# STM32_Minimum_System.net
KiCad netlist of a schematic drawn in EasyEDA Pro
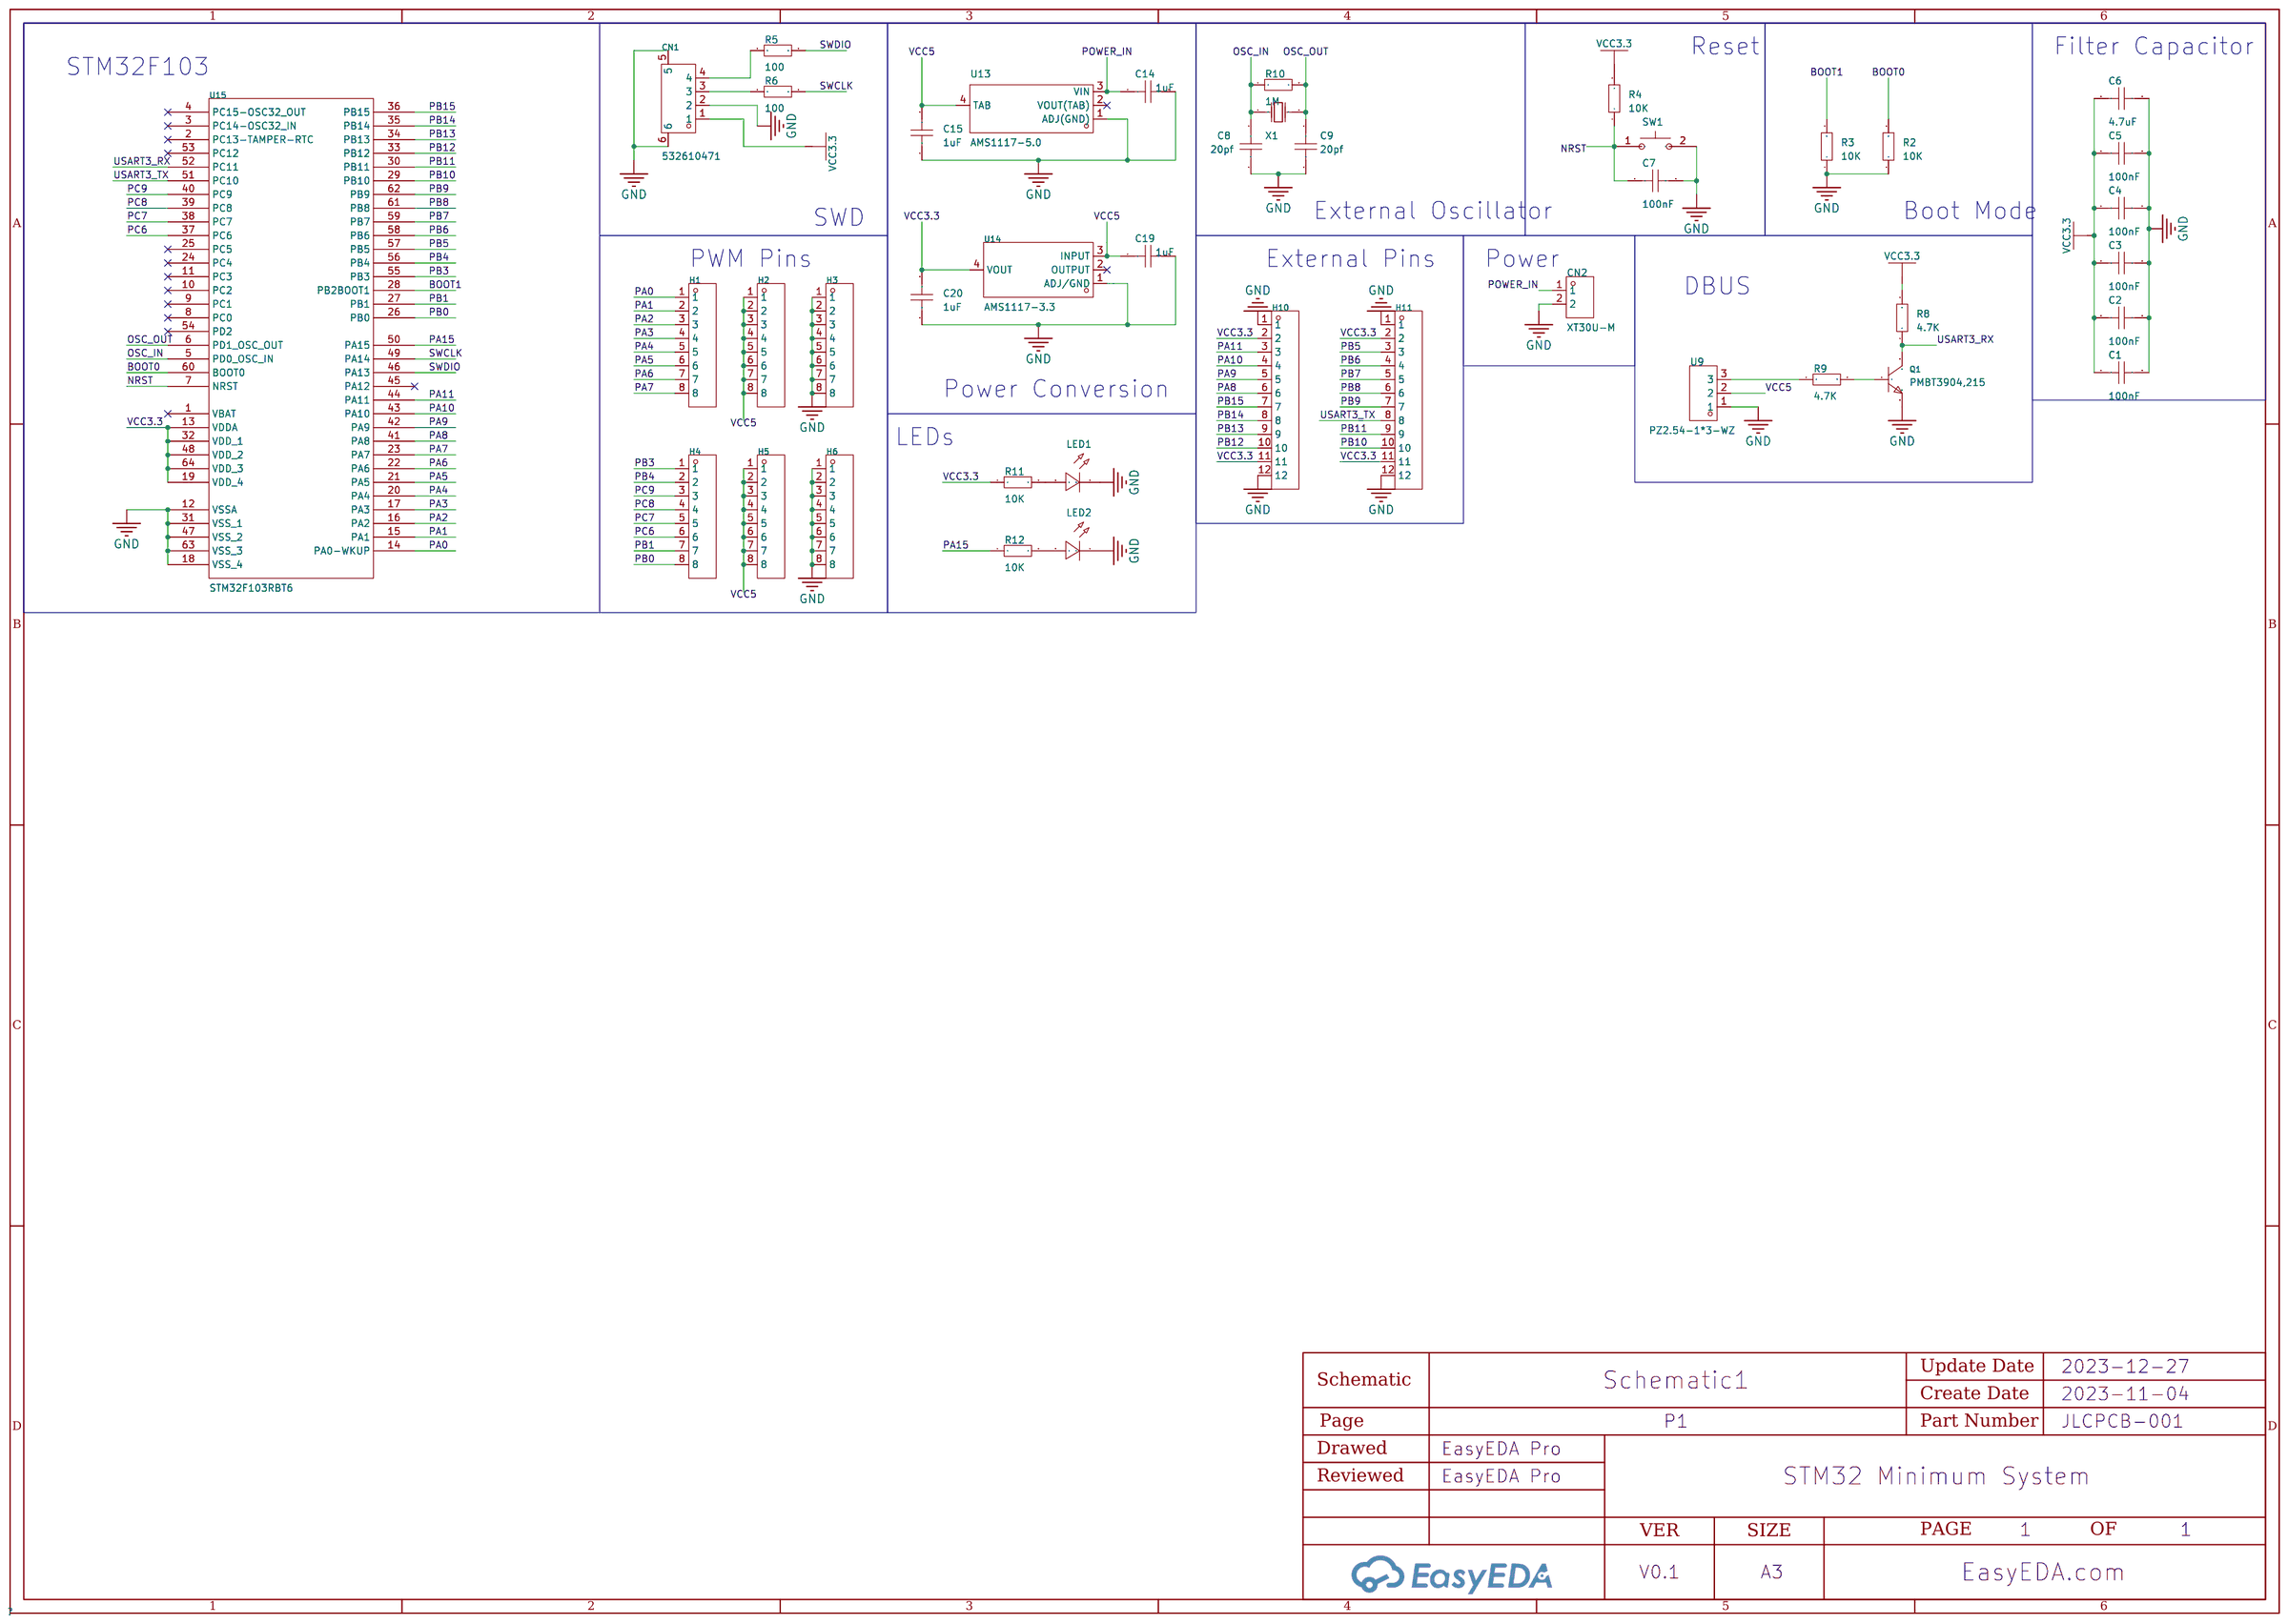
[diagram p0: schematic sheet]

(export (version "E")
  (design (tool "Eeschema 10.0.6"))
  (components
    (comp (ref "C1")
      (value "100nF")
      (footprint "easyedapro:C0603")
      (libsource (lib "easyedapro") (part "CAP"))
    )
    (comp (ref "C2")
      (value "100nF")
      (footprint "easyedapro:C0603")
      (libsource (lib "easyedapro") (part "CAP"))
    )
    (comp (ref "C3")
      (value "100nF")
      (footprint "easyedapro:C0603")
      (libsource (lib "easyedapro") (part "CAP"))
    )
    (comp (ref "C4")
      (value "100nF")
      (footprint "easyedapro:C0603")
      (libsource (lib "easyedapro") (part "CAP"))
    )
    (comp (ref "C5")
      (value "100nF")
      (footprint "easyedapro:C0603")
      (libsource (lib "easyedapro") (part "CAP"))
    )
    (comp (ref "C6")
      (value "4.7uF")
      (footprint "easyedapro:C0603")
      (libsource (lib "easyedapro") (part "CAP"))
    )
    (comp (ref "C7")
      (value "100nF")
      (footprint "easyedapro:C0603")
      (libsource (lib "easyedapro") (part "CAP"))
    )
    (comp (ref "C8")
      (value "20pf")
      (footprint "easyedapro:C0603")
      (libsource (lib "easyedapro") (part "CAP"))
    )
    (comp (ref "C9")
      (value "20pf")
      (footprint "easyedapro:C0603")
      (libsource (lib "easyedapro") (part "CAP"))
    )
    (comp (ref "C14")
      (value "1uF")
      (footprint "easyedapro:C0603")
      (libsource (lib "easyedapro") (part "CAP"))
    )
    (comp (ref "C15")
      (value "1uF")
      (footprint "easyedapro:C0603")
      (libsource (lib "easyedapro") (part "CAP"))
    )
    (comp (ref "C19")
      (value "1uF")
      (footprint "easyedapro:C0603")
      (libsource (lib "easyedapro") (part "CAP"))
    )
    (comp (ref "C20")
      (value "1uF")
      (footprint "easyedapro:C0603")
      (libsource (lib "easyedapro") (part "CAP"))
    )
    (comp (ref "CN1")
      (value "532610471")
      (footprint "easyedapro:CONN-SMD_4P-P1.25_53261-0471")
      (fields (field (name "Manufacturer") "MOLEX"))
      (libsource (lib "easyedapro") (part "53261-0471"))
    )
    (comp (ref "CN2")
      (value "XT30U-M")
      (footprint "easyedapro:CONN-TH_XT30U-M")
      (fields (field (name "Manufacturer") "AMASS(艾迈斯)"))
      (libsource (lib "easyedapro") (part "XT30U-M"))
    )
    (comp (ref "H1")
      (value "KH-2.54PH180-1X8P-L11.5")
      (footprint "easyedapro:HDR-TH_8P-P2.54-V-M")
      (fields (field (name "Manufacturer") "kinghelm(金航标)"))
      (libsource (lib "easyedapro") (part "KH-2.54PH180-1X8P-L11.5"))
    )
    (comp (ref "H2")
      (value "KH-2.54PH180-1X8P-L11.5")
      (footprint "easyedapro:HDR-TH_8P-P2.54-V-M")
      (fields (field (name "Manufacturer") "kinghelm(金航标)"))
      (libsource (lib "easyedapro") (part "KH-2.54PH180-1X8P-L11.5"))
    )
    (comp (ref "H3")
      (value "KH-2.54PH180-1X8P-L11.5")
      (footprint "easyedapro:HDR-TH_8P-P2.54-V-M")
      (fields (field (name "Manufacturer") "kinghelm(金航标)"))
      (libsource (lib "easyedapro") (part "KH-2.54PH180-1X8P-L11.5"))
    )
    (comp (ref "H4")
      (value "KH-2.54PH180-1X8P-L11.5")
      (footprint "easyedapro:HDR-TH_8P-P2.54-V-M")
      (fields (field (name "Manufacturer") "kinghelm(金航标)"))
      (libsource (lib "easyedapro") (part "KH-2.54PH180-1X8P-L11.5"))
    )
    (comp (ref "H5")
      (value "KH-2.54PH180-1X8P-L11.5")
      (footprint "easyedapro:HDR-TH_8P-P2.54-V-M")
      (fields (field (name "Manufacturer") "kinghelm(金航标)"))
      (libsource (lib "easyedapro") (part "KH-2.54PH180-1X8P-L11.5"))
    )
    (comp (ref "H6")
      (value "KH-2.54PH180-1X8P-L11.5")
      (footprint "easyedapro:HDR-TH_8P-P2.54-V-M")
      (fields (field (name "Manufacturer") "kinghelm(金航标)"))
      (libsource (lib "easyedapro") (part "KH-2.54PH180-1X8P-L11.5"))
    )
    (comp (ref "H10")
      (value "KH-2.54PH180-1X12P-L11.5")
      (footprint "easyedapro:HDR-TH_12P-P2.54-V-M")
      (fields (field (name "Manufacturer") "kinghelm(金航标)"))
      (libsource (lib "easyedapro") (part "KH-2.54PH180-1X12P-L11.5"))
    )
    (comp (ref "H11")
      (value "KH-2.54PH180-1X12P-L11.5")
      (footprint "easyedapro:HDR-TH_12P-P2.54-V-M")
      (fields (field (name "Manufacturer") "kinghelm(金航标)"))
      (libsource (lib "easyedapro") (part "KH-2.54PH180-1X12P-L11.5"))
    )
    (comp (ref "LED1")
      (value "~")
      (footprint "easyedapro:LED0603-RD_GREEN")
      (libsource (lib "easyedapro") (part "LED_G"))
    )
    (comp (ref "LED2")
      (value "~")
      (footprint "easyedapro:LED0603-R-RD")
      (libsource (lib "easyedapro") (part "LED_B"))
    )
    (comp (ref "Q1")
      (value "PMBT3904,215")
      (footprint "easyedapro:SOT-23_L2.9-W1.3-P1.90-LS2.4-BR")
      (fields (field (name "Manufacturer") "Nexperia(安世)"))
      (libsource (lib "easyedapro") (part "PMBT3904,215"))
    )
    (comp (ref "R2") (value "10K") (footprint "easyedapro:R0603") (libsource (lib "easyedapro") (part "Res")))
    (comp (ref "R3") (value "10K") (footprint "easyedapro:R0603") (libsource (lib "easyedapro") (part "Res")))
    (comp (ref "R4") (value "10K") (footprint "easyedapro:R0603") (libsource (lib "easyedapro") (part "Res")))
    (comp (ref "R5") (value "100") (footprint "easyedapro:R0603") (libsource (lib "easyedapro") (part "Res")))
    (comp (ref "R6") (value "100") (footprint "easyedapro:R0603") (libsource (lib "easyedapro") (part "Res")))
    (comp (ref "R8")
      (value "4.7K")
      (footprint "easyedapro:R0603")
      (libsource (lib "easyedapro") (part "Res"))
    )
    (comp (ref "R9")
      (value "4.7K")
      (footprint "easyedapro:R0603")
      (libsource (lib "easyedapro") (part "Res"))
    )
    (comp (ref "R10") (value "1M") (footprint "easyedapro:R0603") (libsource (lib "easyedapro") (part "Res")))
    (comp (ref "R11")
      (value "10K")
      (footprint "easyedapro:R0603")
      (libsource (lib "easyedapro") (part "Res"))
    )
    (comp (ref "R12")
      (value "10K")
      (footprint "easyedapro:R0603")
      (libsource (lib "easyedapro") (part "Res"))
    )
    (comp (ref "SW1")
      (value "1TS002C-2300-4300-CT")
      (footprint "easyedapro:SW-SMD_L6.0-W3.5-LS8.0-EH")
      (fields (field (name "Manufacturer") "HYP(鸿源精密)"))
      (libsource (lib "easyedapro") (part "1TS002C-2300-4300"))
    )
    (comp (ref "U9")
      (value "PZ2.54-1*3-WZ")
      (footprint "easyedapro:HDR-TH_3P-P2.54-H-M-W7.7-P")
      (fields (field (name "Manufacturer") "ZHOURI(洲日)"))
      (libsource (lib "easyedapro") (part "PZ2.54-1*3-WZ"))
    )
    (comp (ref "U13")
      (value "AMS1117-5.0")
      (footprint "easyedapro:SOT-223_L6.7-W3.5-P2.30-BR")
      (fields (field (name "Manufacturer") "UMW(广东友台半导体)"))
      (libsource (lib "easyedapro") (part "AMS1117-5.0_C347223"))
    )
    (comp (ref "U14")
      (value "AMS1117-3.3")
      (footprint "easyedapro:SOT-223-3_L6.5-W3.4-P2.30-LS7.0-BR")
      (fields (field (name "Manufacturer") "TECH PUBLIC(台舟)"))
      (libsource (lib "easyedapro") (part "AMS1117-3.3_C18212698"))
    )
    (comp (ref "U15")
      (value "STM32F103RBT6")
      (footprint "easyedapro:LQFP-64_L10.0-W10.0-P0.50-LS12.0-BL")
      (fields (field (name "Manufacturer") "ST(意法半导体)"))
      (libsource (lib "easyedapro") (part "STM32F103RBT6"))
    )
    (comp (ref "X1")
      (value "8MHz")
      (footprint "easyedapro:HC-49US_L11.5-W4.5-P4.88")
      (fields (field (name "Manufacturer Part") "X49SM8MSD2SC") (field (name "Manufacturer") "YXC(扬兴晶振)"))
      (libsource (lib "easyedapro") (part "9B0808LCSC-AAK2S"))
    )
  )
  (nets
    (net (code "1") (name "/BOOT0") (class "Default")
      (node (ref "R2") (pin "2") (pinfunction "2_2") (pintype "input"))
      (node (ref "U15") (pin "60") (pinfunction "BOOT0_60") (pintype "input"))
    )
    (net (code "2") (name "/BOOT1") (class "Default")
      (node (ref "R3") (pin "2") (pinfunction "2_2") (pintype "input"))
      (node (ref "U15") (pin "28") (pinfunction "PB2BOOT1_28") (pintype "input"))
    )
    (net (code "3") (name "/NRST") (class "Default")
      (node (ref "C7") (pin "2") (pinfunction "2_2") (pintype "input"))
      (node (ref "R4") (pin "1") (pinfunction "1_1") (pintype "input"))
      (node (ref "SW1") (pin "1") (pinfunction "A_1") (pintype "input"))
      (node (ref "U15") (pin "7") (pinfunction "NRST_7") (pintype "input"))
    )
    (net (code "4") (name "/OSC_IN") (class "Default")
      (node (ref "C8") (pin "1") (pinfunction "1_1") (pintype "input"))
      (node (ref "R10") (pin "1") (pinfunction "1_1") (pintype "input"))
      (node (ref "U15") (pin "5") (pinfunction "PD0_OSC_IN_5") (pintype "input"))
      (node (ref "X1") (pin "1") (pinfunction "OSC1_1") (pintype "input"))
    )
    (net (code "5") (name "/OSC_OUT") (class "Default")
      (node (ref "C9") (pin "1") (pinfunction "1_1") (pintype "input"))
      (node (ref "R10") (pin "2") (pinfunction "2_2") (pintype "input"))
      (node (ref "U15") (pin "6") (pinfunction "PD1_OSC_OUT_6") (pintype "input"))
      (node (ref "X1") (pin "2") (pinfunction "OSC2_2") (pintype "input"))
    )
    (net (code "6") (name "/PA0") (class "Default")
      (node (ref "H1") (pin "1") (pinfunction "1_1") (pintype "input"))
      (node (ref "U15") (pin "14") (pinfunction "PA0-WKUP_14") (pintype "input"))
    )
    (net (code "7") (name "/PA1") (class "Default")
      (node (ref "H1") (pin "2") (pinfunction "2_2") (pintype "input"))
      (node (ref "U15") (pin "15") (pinfunction "PA1_15") (pintype "input"))
    )
    (net (code "8") (name "/PA2") (class "Default")
      (node (ref "H1") (pin "3") (pinfunction "3_3") (pintype "input"))
      (node (ref "U15") (pin "16") (pinfunction "PA2_16") (pintype "input"))
    )
    (net (code "9") (name "/PA3") (class "Default")
      (node (ref "H1") (pin "4") (pinfunction "4_4") (pintype "input"))
      (node (ref "U15") (pin "17") (pinfunction "PA3_17") (pintype "input"))
    )
    (net (code "10") (name "/PA4") (class "Default")
      (node (ref "H1") (pin "5") (pinfunction "5_5") (pintype "input"))
      (node (ref "U15") (pin "20") (pinfunction "PA4_20") (pintype "input"))
    )
    (net (code "11") (name "/PA5") (class "Default")
      (node (ref "H1") (pin "6") (pinfunction "6_6") (pintype "input"))
      (node (ref "U15") (pin "21") (pinfunction "PA5_21") (pintype "input"))
    )
    (net (code "12") (name "/PA6") (class "Default")
      (node (ref "H1") (pin "7") (pinfunction "7_7") (pintype "input"))
      (node (ref "U15") (pin "22") (pinfunction "PA6_22") (pintype "input"))
    )
    (net (code "13") (name "/PA7") (class "Default")
      (node (ref "H1") (pin "8") (pinfunction "8_8") (pintype "input"))
      (node (ref "U15") (pin "23") (pinfunction "PA7_23") (pintype "input"))
    )
    (net (code "14") (name "/PA8") (class "Default")
      (node (ref "H10") (pin "6") (pinfunction "6_6") (pintype "input"))
      (node (ref "U15") (pin "41") (pinfunction "PA8_41") (pintype "input"))
    )
    (net (code "15") (name "/PA9") (class "Default")
      (node (ref "H10") (pin "5") (pinfunction "5_5") (pintype "input"))
      (node (ref "U15") (pin "42") (pinfunction "PA9_42") (pintype "input"))
    )
    (net (code "16") (name "/PA10") (class "Default")
      (node (ref "H10") (pin "4") (pinfunction "4_4") (pintype "input"))
      (node (ref "U15") (pin "43") (pinfunction "PA10_43") (pintype "input"))
    )
    (net (code "17") (name "/PA11") (class "Default")
      (node (ref "H10") (pin "3") (pinfunction "3_3") (pintype "input"))
      (node (ref "U15") (pin "44") (pinfunction "PA11_44") (pintype "input"))
    )
    (net (code "18") (name "/PA15") (class "Default")
      (node (ref "R12") (pin "1") (pinfunction "1_1") (pintype "input"))
      (node (ref "U15") (pin "50") (pinfunction "PA15_50") (pintype "input"))
    )
    (net (code "19") (name "/PB0") (class "Default")
      (node (ref "H4") (pin "8") (pinfunction "8_8") (pintype "input"))
      (node (ref "U15") (pin "26") (pinfunction "PB0_26") (pintype "input"))
    )
    (net (code "20") (name "/PB1") (class "Default")
      (node (ref "H4") (pin "7") (pinfunction "7_7") (pintype "input"))
      (node (ref "U15") (pin "27") (pinfunction "PB1_27") (pintype "input"))
    )
    (net (code "21") (name "/PB3") (class "Default")
      (node (ref "H4") (pin "1") (pinfunction "1_1") (pintype "input"))
      (node (ref "U15") (pin "55") (pinfunction "PB3_55") (pintype "input"))
    )
    (net (code "22") (name "/PB4") (class "Default")
      (node (ref "H4") (pin "2") (pinfunction "2_2") (pintype "input"))
      (node (ref "U15") (pin "56") (pinfunction "PB4_56") (pintype "input"))
    )
    (net (code "23") (name "/PB5") (class "Default")
      (node (ref "H11") (pin "3") (pinfunction "3_3") (pintype "input"))
      (node (ref "U15") (pin "57") (pinfunction "PB5_57") (pintype "input"))
    )
    (net (code "24") (name "/PB6") (class "Default")
      (node (ref "H11") (pin "4") (pinfunction "4_4") (pintype "input"))
      (node (ref "U15") (pin "58") (pinfunction "PB6_58") (pintype "input"))
    )
    (net (code "25") (name "/PB7") (class "Default")
      (node (ref "H11") (pin "5") (pinfunction "5_5") (pintype "input"))
      (node (ref "U15") (pin "59") (pinfunction "PB7_59") (pintype "input"))
    )
    (net (code "26") (name "/PB8") (class "Default")
      (node (ref "H11") (pin "6") (pinfunction "6_6") (pintype "input"))
      (node (ref "U15") (pin "61") (pinfunction "PB8_61") (pintype "input"))
    )
    (net (code "27") (name "/PB9") (class "Default")
      (node (ref "H11") (pin "7") (pinfunction "7_7") (pintype "input"))
      (node (ref "U15") (pin "62") (pinfunction "PB9_62") (pintype "input"))
    )
    (net (code "28") (name "/PB10") (class "Default")
      (node (ref "H11") (pin "10") (pinfunction "10_10") (pintype "input"))
      (node (ref "U15") (pin "29") (pinfunction "PB10_29") (pintype "input"))
    )
    (net (code "29") (name "/PB11") (class "Default")
      (node (ref "H11") (pin "9") (pinfunction "9_9") (pintype "input"))
      (node (ref "U15") (pin "30") (pinfunction "PB11_30") (pintype "input"))
    )
    (net (code "30") (name "/PB12") (class "Default")
      (node (ref "H10") (pin "10") (pinfunction "10_10") (pintype "input"))
      (node (ref "U15") (pin "33") (pinfunction "PB12_33") (pintype "input"))
    )
    (net (code "31") (name "/PB13") (class "Default")
      (node (ref "H10") (pin "9") (pinfunction "9_9") (pintype "input"))
      (node (ref "U15") (pin "34") (pinfunction "PB13_34") (pintype "input"))
    )
    (net (code "32") (name "/PB14") (class "Default")
      (node (ref "H10") (pin "8") (pinfunction "8_8") (pintype "input"))
      (node (ref "U15") (pin "35") (pinfunction "PB14_35") (pintype "input"))
    )
    (net (code "33") (name "/PB15") (class "Default")
      (node (ref "H10") (pin "7") (pinfunction "7_7") (pintype "input"))
      (node (ref "U15") (pin "36") (pinfunction "PB15_36") (pintype "input"))
    )
    (net (code "34") (name "/PC6") (class "Default")
      (node (ref "H4") (pin "6") (pinfunction "6_6") (pintype "input"))
      (node (ref "U15") (pin "37") (pinfunction "PC6_37") (pintype "input"))
    )
    (net (code "35") (name "/PC7") (class "Default")
      (node (ref "H4") (pin "5") (pinfunction "5_5") (pintype "input"))
      (node (ref "U15") (pin "38") (pinfunction "PC7_38") (pintype "input"))
    )
    (net (code "36") (name "/PC8") (class "Default")
      (node (ref "H4") (pin "4") (pinfunction "4_4") (pintype "input"))
      (node (ref "U15") (pin "39") (pinfunction "PC8_39") (pintype "input"))
    )
    (net (code "37") (name "/PC9") (class "Default")
      (node (ref "H4") (pin "3") (pinfunction "3_3") (pintype "input"))
      (node (ref "U15") (pin "40") (pinfunction "PC9_40") (pintype "input"))
    )
    (net (code "38") (name "/POWER_IN") (class "Default")
      (node (ref "C14") (pin "1") (pinfunction "1_1") (pintype "input"))
      (node (ref "CN2") (pin "1") (pinfunction "1_1") (pintype "input"))
      (node (ref "U13") (pin "3") (pinfunction "VIN_3") (pintype "input"))
    )
    (net (code "39") (name "/SWCLK") (class "Default")
      (node (ref "R6") (pin "2") (pinfunction "2_2") (pintype "input"))
      (node (ref "U15") (pin "49") (pinfunction "PA14_49") (pintype "input"))
    )
    (net (code "40") (name "/SWDIO") (class "Default")
      (node (ref "R5") (pin "2") (pinfunction "2_2") (pintype "input"))
      (node (ref "U15") (pin "46") (pinfunction "PA13_46") (pintype "input"))
    )
    (net (code "41") (name "/USART3_RX") (class "Default")
      (node (ref "Q1") (pin "3") (pinfunction "3_3") (pintype "input"))
      (node (ref "R8") (pin "1") (pinfunction "1_1") (pintype "input"))
      (node (ref "U15") (pin "52") (pinfunction "PC11_52") (pintype "input"))
    )
    (net (code "42") (name "/USART3_TX") (class "Default")
      (node (ref "H11") (pin "8") (pinfunction "8_8") (pintype "input"))
      (node (ref "U15") (pin "51") (pinfunction "PC10_51") (pintype "input"))
    )
    (net (code "43") (name "/VCC5") (class "Default")
      (node (ref "C15") (pin "2") (pinfunction "2_2") (pintype "input"))
      (node (ref "C19") (pin "1") (pinfunction "1_1") (pintype "input"))
      (node (ref "H2") (pin "1") (pinfunction "1_1") (pintype "input"))
      (node (ref "H2") (pin "2") (pinfunction "2_2") (pintype "input"))
      (node (ref "H2") (pin "3") (pinfunction "3_3") (pintype "input"))
      (node (ref "H2") (pin "4") (pinfunction "4_4") (pintype "input"))
      (node (ref "H2") (pin "5") (pinfunction "5_5") (pintype "input"))
      (node (ref "H2") (pin "6") (pinfunction "6_6") (pintype "input"))
      (node (ref "H2") (pin "7") (pinfunction "7_7") (pintype "input"))
      (node (ref "H2") (pin "8") (pinfunction "8_8") (pintype "input"))
      (node (ref "H5") (pin "1") (pinfunction "1_1") (pintype "input"))
      (node (ref "H5") (pin "2") (pinfunction "2_2") (pintype "input"))
      (node (ref "H5") (pin "3") (pinfunction "3_3") (pintype "input"))
      (node (ref "H5") (pin "4") (pinfunction "4_4") (pintype "input"))
      (node (ref "H5") (pin "5") (pinfunction "5_5") (pintype "input"))
      (node (ref "H5") (pin "6") (pinfunction "6_6") (pintype "input"))
      (node (ref "H5") (pin "7") (pinfunction "7_7") (pintype "input"))
      (node (ref "H5") (pin "8") (pinfunction "8_8") (pintype "input"))
      (node (ref "U13") (pin "4") (pinfunction "TAB_4") (pintype "input"))
      (node (ref "U14") (pin "3") (pinfunction "INPUT_3") (pintype "input"))
      (node (ref "U9") (pin "2") (pinfunction "2_2") (pintype "input"))
    )
    (net (code "44") (name "GND") (class "Default")
      (node (ref "C1") (pin "2") (pinfunction "2_2") (pintype "input"))
      (node (ref "C14") (pin "2") (pinfunction "2_2") (pintype "input"))
      (node (ref "C15") (pin "1") (pinfunction "1_1") (pintype "input"))
      (node (ref "C19") (pin "2") (pinfunction "2_2") (pintype "input"))
      (node (ref "C2") (pin "2") (pinfunction "2_2") (pintype "input"))
      (node (ref "C20") (pin "1") (pinfunction "1_1") (pintype "input"))
      (node (ref "C3") (pin "2") (pinfunction "2_2") (pintype "input"))
      (node (ref "C4") (pin "2") (pinfunction "2_2") (pintype "input"))
      (node (ref "C5") (pin "2") (pinfunction "2_2") (pintype "input"))
      (node (ref "C6") (pin "2") (pinfunction "2_2") (pintype "input"))
      (node (ref "C7") (pin "1") (pinfunction "1_1") (pintype "input"))
      (node (ref "C8") (pin "2") (pinfunction "2_2") (pintype "input"))
      (node (ref "C9") (pin "2") (pinfunction "2_2") (pintype "input"))
      (node (ref "CN1") (pin "2") (pinfunction "2_2") (pintype "input"))
      (node (ref "CN1") (pin "5") (pinfunction "5_5") (pintype "input"))
      (node (ref "CN1") (pin "6") (pinfunction "6_6") (pintype "input"))
      (node (ref "CN2") (pin "2") (pinfunction "2_2") (pintype "input"))
      (node (ref "H10") (pin "1") (pinfunction "1_1") (pintype "input"))
      (node (ref "H10") (pin "12") (pinfunction "12_12") (pintype "input"))
      (node (ref "H11") (pin "1") (pinfunction "1_1") (pintype "input"))
      (node (ref "H11") (pin "12") (pinfunction "12_12") (pintype "input"))
      (node (ref "H3") (pin "1") (pinfunction "1_1") (pintype "input"))
      (node (ref "H3") (pin "2") (pinfunction "2_2") (pintype "input"))
      (node (ref "H3") (pin "3") (pinfunction "3_3") (pintype "input"))
      (node (ref "H3") (pin "4") (pinfunction "4_4") (pintype "input"))
      (node (ref "H3") (pin "5") (pinfunction "5_5") (pintype "input"))
      (node (ref "H3") (pin "6") (pinfunction "6_6") (pintype "input"))
      (node (ref "H3") (pin "7") (pinfunction "7_7") (pintype "input"))
      (node (ref "H3") (pin "8") (pinfunction "8_8") (pintype "input"))
      (node (ref "H6") (pin "1") (pinfunction "1_1") (pintype "input"))
      (node (ref "H6") (pin "2") (pinfunction "2_2") (pintype "input"))
      (node (ref "H6") (pin "3") (pinfunction "3_3") (pintype "input"))
      (node (ref "H6") (pin "4") (pinfunction "4_4") (pintype "input"))
      (node (ref "H6") (pin "5") (pinfunction "5_5") (pintype "input"))
      (node (ref "H6") (pin "6") (pinfunction "6_6") (pintype "input"))
      (node (ref "H6") (pin "7") (pinfunction "7_7") (pintype "input"))
      (node (ref "H6") (pin "8") (pinfunction "8_8") (pintype "input"))
      (node (ref "LED1") (pin "1") (pinfunction "C_1") (pintype "input"))
      (node (ref "LED2") (pin "1") (pinfunction "C_1") (pintype "input"))
      (node (ref "Q1") (pin "2") (pinfunction "2_2") (pintype "input"))
      (node (ref "R2") (pin "1") (pinfunction "1_1") (pintype "input"))
      (node (ref "R3") (pin "1") (pinfunction "1_1") (pintype "input"))
      (node (ref "SW1") (pin "2") (pinfunction "B_2") (pintype "input"))
      (node (ref "U13") (pin "1") (pinfunction "ADJ(GND)_1") (pintype "input"))
      (node (ref "U14") (pin "1") (pinfunction "ADJ/GND_1") (pintype "input"))
      (node (ref "U15") (pin "12") (pinfunction "VSSA_12") (pintype "input"))
      (node (ref "U15") (pin "18") (pinfunction "VSS_4_18") (pintype "input"))
      (node (ref "U15") (pin "31") (pinfunction "VSS_1_31") (pintype "input"))
      (node (ref "U15") (pin "47") (pinfunction "VSS_2_47") (pintype "input"))
      (node (ref "U15") (pin "63") (pinfunction "VSS_3_63") (pintype "input"))
      (node (ref "U9") (pin "1") (pinfunction "1_1") (pintype "input"))
    )
    (net (code "45") (name "Net-(CN1-Pad3)") (class "Default")
      (node (ref "CN1") (pin "3") (pinfunction "3_3") (pintype "input"))
      (node (ref "R6") (pin "1") (pinfunction "1_1") (pintype "input"))
    )
    (net (code "46") (name "Net-(CN1-Pad4)") (class "Default")
      (node (ref "CN1") (pin "4") (pinfunction "4_4") (pintype "input"))
      (node (ref "R5") (pin "1") (pinfunction "1_1") (pintype "input"))
    )
    (net (code "47") (name "Net-(LED1-A)") (class "Default")
      (node (ref "LED1") (pin "2") (pinfunction "A_2") (pintype "input"))
      (node (ref "R11") (pin "2") (pinfunction "2_2") (pintype "input"))
    )
    (net (code "48") (name "Net-(LED2-A)") (class "Default")
      (node (ref "LED2") (pin "2") (pinfunction "A_2") (pintype "input"))
      (node (ref "R12") (pin "2") (pinfunction "2_2") (pintype "input"))
    )
    (net (code "49") (name "Net-(Q1-Pad1)") (class "Default")
      (node (ref "Q1") (pin "1") (pinfunction "1_1") (pintype "input"))
      (node (ref "R9") (pin "2") (pinfunction "2_2") (pintype "input"))
    )
    (net (code "50") (name "Net-(R9-Pad1)") (class "Default")
      (node (ref "R9") (pin "1") (pinfunction "1_1") (pintype "input"))
      (node (ref "U9") (pin "3") (pinfunction "3_3") (pintype "input"))
    )
    (net (code "51") (name "VCC3.3") (class "Default")
      (node (ref "C1") (pin "1") (pinfunction "1_1") (pintype "input"))
      (node (ref "C2") (pin "1") (pinfunction "1_1") (pintype "input"))
      (node (ref "C20") (pin "2") (pinfunction "2_2") (pintype "input"))
      (node (ref "C3") (pin "1") (pinfunction "1_1") (pintype "input"))
      (node (ref "C4") (pin "1") (pinfunction "1_1") (pintype "input"))
      (node (ref "C5") (pin "1") (pinfunction "1_1") (pintype "input"))
      (node (ref "C6") (pin "1") (pinfunction "1_1") (pintype "input"))
      (node (ref "CN1") (pin "1") (pinfunction "1_1") (pintype "input"))
      (node (ref "H10") (pin "11") (pinfunction "11_11") (pintype "input"))
      (node (ref "H10") (pin "2") (pinfunction "2_2") (pintype "input"))
      (node (ref "H11") (pin "11") (pinfunction "11_11") (pintype "input"))
      (node (ref "H11") (pin "2") (pinfunction "2_2") (pintype "input"))
      (node (ref "R11") (pin "1") (pinfunction "1_1") (pintype "input"))
      (node (ref "R4") (pin "2") (pinfunction "2_2") (pintype "input"))
      (node (ref "R8") (pin "2") (pinfunction "2_2") (pintype "input"))
      (node (ref "U14") (pin "4") (pinfunction "VOUT_4") (pintype "input"))
      (node (ref "U15") (pin "13") (pinfunction "VDDA_13") (pintype "input"))
      (node (ref "U15") (pin "19") (pinfunction "VDD_4_19") (pintype "input"))
      (node (ref "U15") (pin "32") (pinfunction "VDD_1_32") (pintype "input"))
      (node (ref "U15") (pin "48") (pinfunction "VDD_2_48") (pintype "input"))
      (node (ref "U15") (pin "64") (pinfunction "VDD_3_64") (pintype "input"))
    )
    (net (code "52") (name "unconnected-(U13-VOUT(TAB)-Pad2)") (class "Default")
      (node (ref "U13") (pin "2") (pinfunction "VOUT(TAB)_2") (pintype "input+no_connect"))
    )
    (net (code "53") (name "unconnected-(U14-OUTPUT-Pad2)") (class "Default")
      (node (ref "U14") (pin "2") (pinfunction "OUTPUT_2") (pintype "input+no_connect"))
    )
    (net (code "54") (name "unconnected-(U15-PA12-Pad45)") (class "Default")
      (node (ref "U15") (pin "45") (pinfunction "PA12_45") (pintype "input+no_connect"))
    )
    (net (code "55") (name "unconnected-(U15-PC0-Pad8)") (class "Default")
      (node (ref "U15") (pin "8") (pinfunction "PC0_8") (pintype "input+no_connect"))
    )
    (net (code "56") (name "unconnected-(U15-PC1-Pad9)") (class "Default")
      (node (ref "U15") (pin "9") (pinfunction "PC1_9") (pintype "input+no_connect"))
    )
    (net (code "57") (name "unconnected-(U15-PC2-Pad10)") (class "Default")
      (node (ref "U15") (pin "10") (pinfunction "PC2_10") (pintype "input+no_connect"))
    )
    (net (code "58") (name "unconnected-(U15-PC3-Pad11)") (class "Default")
      (node (ref "U15") (pin "11") (pinfunction "PC3_11") (pintype "input+no_connect"))
    )
    (net (code "59") (name "unconnected-(U15-PC4-Pad24)") (class "Default")
      (node (ref "U15") (pin "24") (pinfunction "PC4_24") (pintype "input+no_connect"))
    )
    (net (code "60") (name "unconnected-(U15-PC5-Pad25)") (class "Default")
      (node (ref "U15") (pin "25") (pinfunction "PC5_25") (pintype "input+no_connect"))
    )
    (net (code "61") (name "unconnected-(U15-PC12-Pad53)") (class "Default")
      (node (ref "U15") (pin "53") (pinfunction "PC12_53") (pintype "input+no_connect"))
    )
    (net (code "62") (name "unconnected-(U15-PC13-TAMPER-RTC-Pad2)") (class "Default")
      (node (ref "U15") (pin "2") (pinfunction "PC13-TAMPER-RTC_2") (pintype "input+no_connect"))
    )
    (net (code "63") (name "unconnected-(U15-PC14-OSC32_IN-Pad3)") (class "Default")
      (node (ref "U15") (pin "3") (pinfunction "PC14-OSC32_IN_3") (pintype "input+no_connect"))
    )
    (net (code "64") (name "unconnected-(U15-PC15-OSC32_OUT-Pad4)") (class "Default")
      (node (ref "U15") (pin "4") (pinfunction "PC15-OSC32_OUT_4") (pintype "input+no_connect"))
    )
    (net (code "65") (name "unconnected-(U15-PD2-Pad54)") (class "Default")
      (node (ref "U15") (pin "54") (pinfunction "PD2_54") (pintype "input+no_connect"))
    )
    (net (code "66") (name "unconnected-(U15-VBAT-Pad1)") (class "Default")
      (node (ref "U15") (pin "1") (pinfunction "VBAT_1") (pintype "input+no_connect"))
    )
  )
)
